# Touch.net
KiCad netlist of a schematic drawn in Altium Designer
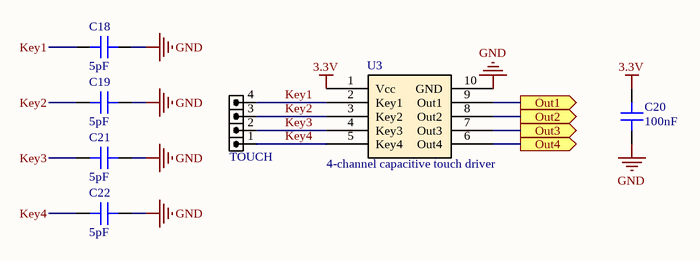
[diagram p0: Touch.SchDoc]

(export (version "E")
  (design (tool "Eeschema 10.0.6"))
  (components
    (comp (ref "C18")
      (value "5pF")
      (footprint "CAP 0603_1608")
      (description "SMT Capacitor")
      (libsource (lib "Capacitor") (part "Cap 0603"))
    )
    (comp (ref "C19")
      (value "5pF")
      (footprint "CAP 0603_1608")
      (description "SMT Capacitor")
      (libsource (lib "Capacitor") (part "Cap 0603"))
    )
    (comp (ref "C20")
      (value "100nF")
      (footprint "CAP 0603_1608")
      (description "SMT Capacitor")
      (libsource (lib "Capacitor") (part "Cap 0603"))
    )
    (comp (ref "C21")
      (value "5pF")
      (footprint "CAP 0603_1608")
      (description "SMT Capacitor")
      (libsource (lib "Capacitor") (part "Cap 0603"))
    )
    (comp (ref "C22")
      (value "5pF")
      (footprint "CAP 0603_1608")
      (description "SMT Capacitor")
      (libsource (lib "Capacitor") (part "Cap 0603"))
    )
    (comp (ref "TOUCH")
      (value "HDR4")
      (footprint "HDR1SE_M_1X4")
      (description "HEADER, 1mm pitch, test, SMD")
      (libsource (lib "Conn Header") (part "HDRTST_1X4"))
    )
    (comp (ref "U3")
      (value "4-channel capacitive touch driver")
      (footprint "MSOP-10")
      (libsource (lib "Salman_lib") (part "BS814A-1"))
    )
  )
  (nets
    (net (code "1") (name "/Key1") (class "Default")
      (node (ref "C18") (pin "1") (pinfunction "1_1") (pintype "passive"))
      (node (ref "TOUCH") (pin "4") (pinfunction "4_4") (pintype "passive"))
      (node (ref "U3") (pin "2") (pinfunction "Key1_2") (pintype "passive"))
    )
    (net (code "2") (name "/Key2") (class "Default")
      (node (ref "C19") (pin "1") (pinfunction "1_1") (pintype "passive"))
      (node (ref "TOUCH") (pin "3") (pinfunction "3_3") (pintype "passive"))
      (node (ref "U3") (pin "3") (pinfunction "Key2_3") (pintype "passive"))
    )
    (net (code "3") (name "/Key3") (class "Default")
      (node (ref "C21") (pin "1") (pinfunction "1_1") (pintype "passive"))
      (node (ref "TOUCH") (pin "2") (pinfunction "2_2") (pintype "passive"))
      (node (ref "U3") (pin "4") (pinfunction "Key3_4") (pintype "passive"))
    )
    (net (code "4") (name "/Key4") (class "Default")
      (node (ref "C22") (pin "1") (pinfunction "1_1") (pintype "passive"))
      (node (ref "TOUCH") (pin "1") (pinfunction "1_1") (pintype "passive"))
      (node (ref "U3") (pin "5") (pinfunction "Key4_5") (pintype "passive"))
    )
    (net (code "5") (name "/Out1") (class "Default")
      (node (ref "U3") (pin "9") (pinfunction "Out1_9") (pintype "passive"))
    )
    (net (code "6") (name "/Out2") (class "Default")
      (node (ref "U3") (pin "8") (pinfunction "Out2_8") (pintype "passive"))
    )
    (net (code "7") (name "/Out3") (class "Default")
      (node (ref "U3") (pin "7") (pinfunction "Out3_7") (pintype "passive"))
    )
    (net (code "8") (name "/Out4") (class "Default")
      (node (ref "U3") (pin "6") (pinfunction "Out4_6") (pintype "passive"))
    )
    (net (code "9") (name "3.3V") (class "Default")
      (node (ref "C20") (pin "2") (pinfunction "2_2") (pintype "passive"))
      (node (ref "U3") (pin "1") (pinfunction "Vcc_1") (pintype "passive"))
    )
    (net (code "10") (name "GND") (class "Default")
      (node (ref "C18") (pin "2") (pinfunction "2_2") (pintype "passive"))
      (node (ref "C19") (pin "2") (pinfunction "2_2") (pintype "passive"))
      (node (ref "C20") (pin "1") (pinfunction "1_1") (pintype "passive"))
      (node (ref "C21") (pin "2") (pinfunction "2_2") (pintype "passive"))
      (node (ref "C22") (pin "2") (pinfunction "2_2") (pintype "passive"))
      (node (ref "U3") (pin "10") (pinfunction "GND_10") (pintype "passive"))
    )
  )
)
